# Oven_Control.net
KiCad netlist of a schematic drawn in EAGLE
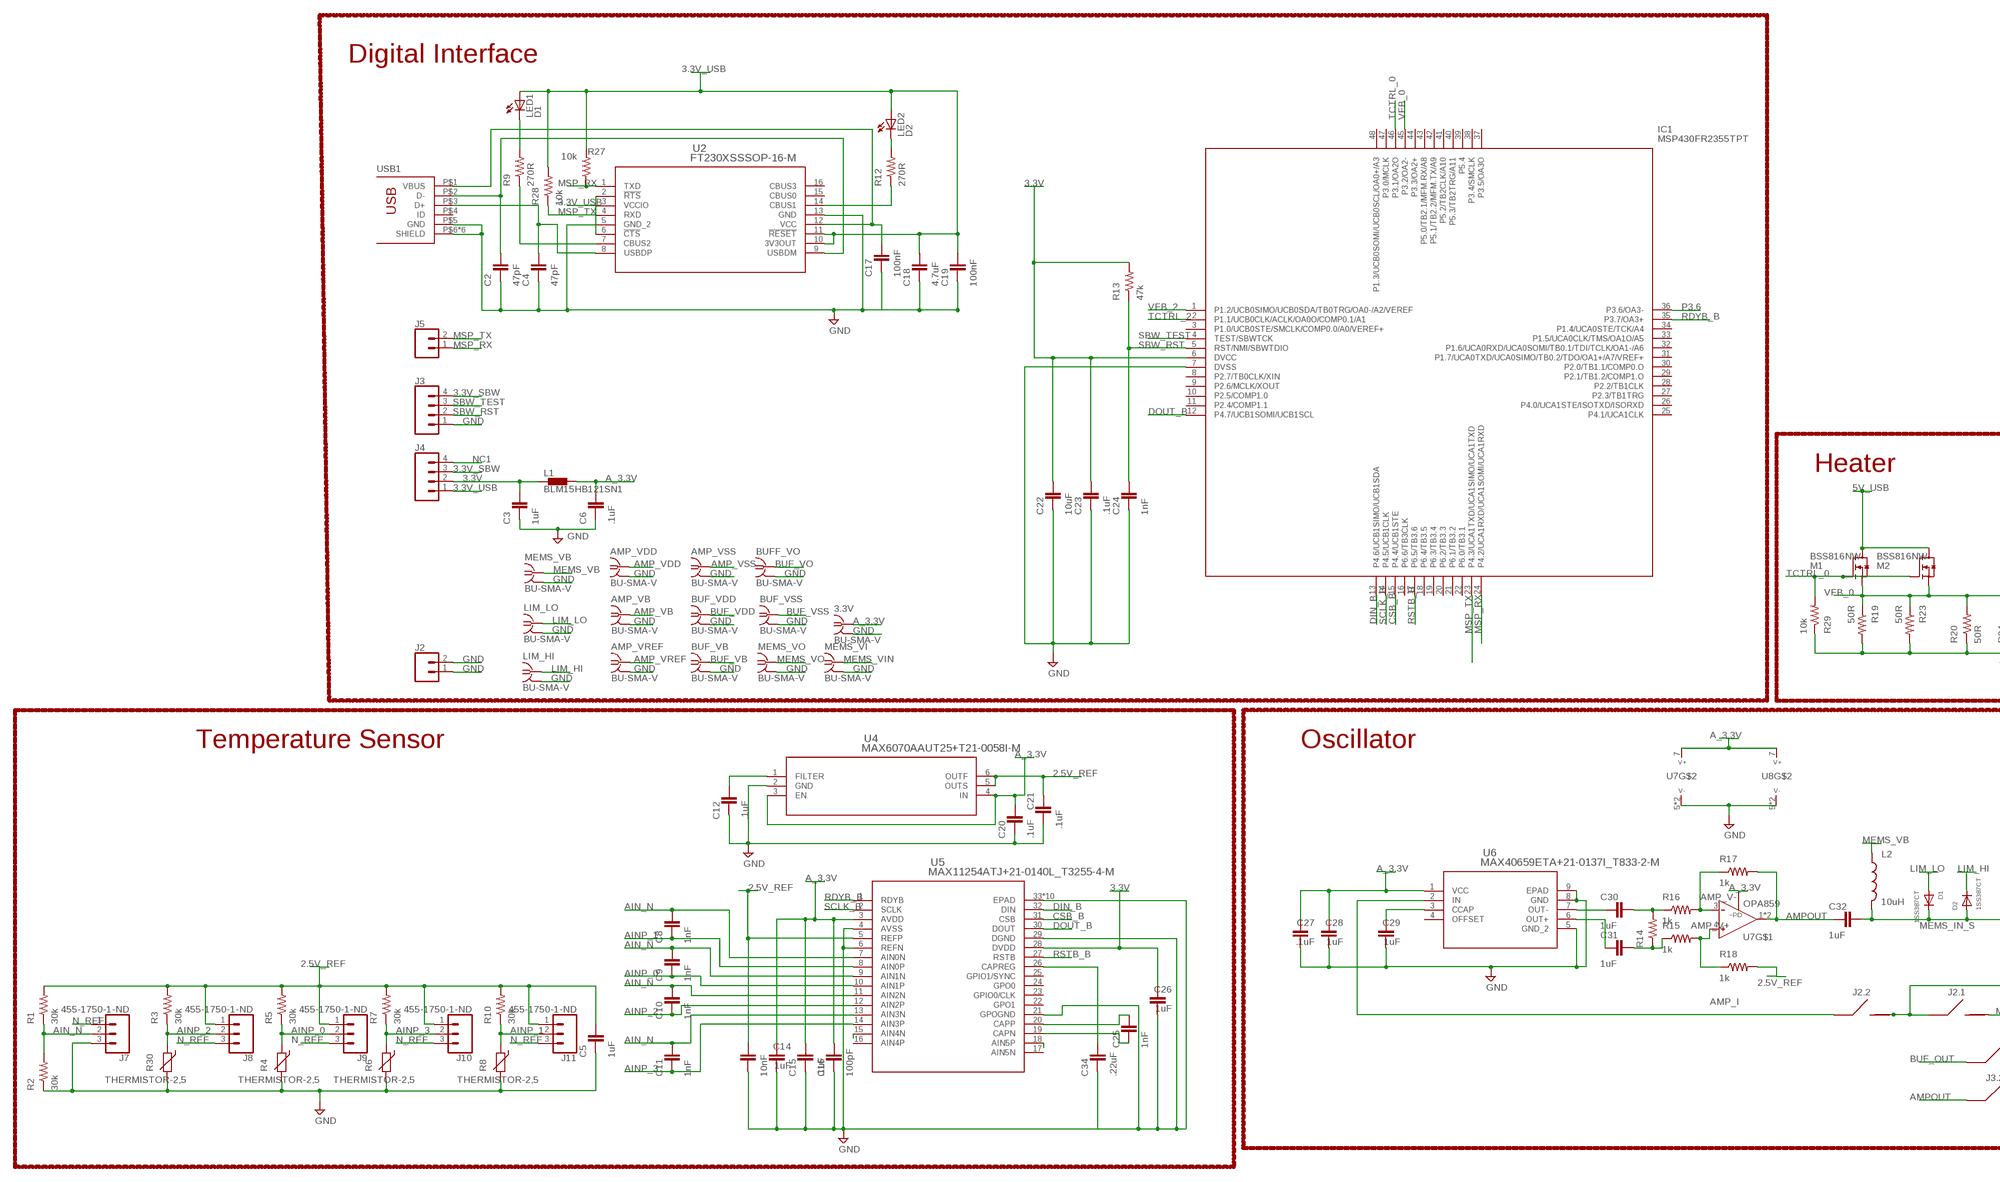
[diagram p0: schematic, sheet 1, part 1 of 2]
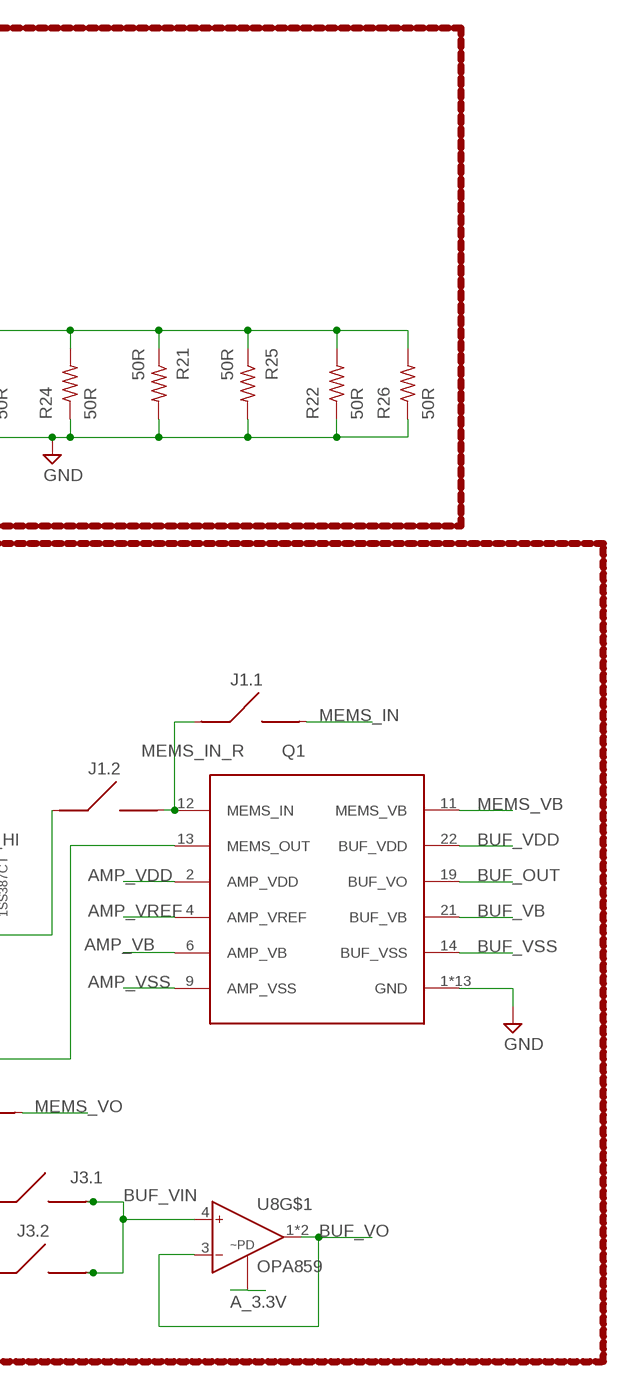
[diagram p1: schematic, sheet 1, part 2 of 2]

(export (version "E")
  (design (tool "Eeschema 10.0.6"))
  (components
    (comp (ref "3.3V")
      (value "BU-SMA-V")
      (footprint "eagle-import:BU-SMA-V")
      (libsource (lib "eagle-import") (part "BU-SMA-V"))
    )
    (comp (ref "AMP_VB")
      (value "BU-SMA-V")
      (footprint "eagle-import:BU-SMA-V")
      (libsource (lib "eagle-import") (part "BU-SMA-V"))
    )
    (comp (ref "AMP_VDD")
      (value "BU-SMA-V")
      (footprint "eagle-import:BU-SMA-V")
      (libsource (lib "eagle-import") (part "BU-SMA-V"))
    )
    (comp (ref "AMP_VREF")
      (value "BU-SMA-V")
      (footprint "eagle-import:BU-SMA-V")
      (libsource (lib "eagle-import") (part "BU-SMA-V"))
    )
    (comp (ref "AMP_VSS")
      (value "BU-SMA-V")
      (footprint "eagle-import:BU-SMA-V")
      (libsource (lib "eagle-import") (part "BU-SMA-V"))
    )
    (comp (ref "BUFF_VO")
      (value "BU-SMA-V")
      (footprint "eagle-import:BU-SMA-V")
      (libsource (lib "eagle-import") (part "BU-SMA-V"))
    )
    (comp (ref "BUF_VB")
      (value "BU-SMA-V")
      (footprint "eagle-import:BU-SMA-V")
      (libsource (lib "eagle-import") (part "BU-SMA-V"))
    )
    (comp (ref "BUF_VDD")
      (value "BU-SMA-V")
      (footprint "eagle-import:BU-SMA-V")
      (libsource (lib "eagle-import") (part "BU-SMA-V"))
    )
    (comp (ref "BUF_VSS")
      (value "BU-SMA-V")
      (footprint "eagle-import:BU-SMA-V")
      (libsource (lib "eagle-import") (part "BU-SMA-V"))
    )
    (comp (ref "C2")
      (value "47pF")
      (footprint "eagle-import:0402-CAP")
      (libsource (lib "eagle-import") (part "CAP0402-CAP"))
    )
    (comp (ref "C3")
      (value "1uF")
      (footprint "eagle-import:0402-CAP")
      (libsource (lib "eagle-import") (part "CAP0402-CAP"))
    )
    (comp (ref "C4")
      (value "47pF")
      (footprint "eagle-import:0402-CAP")
      (libsource (lib "eagle-import") (part "CAP0402-CAP"))
    )
    (comp (ref "C5")
      (value "1uF")
      (footprint "eagle-import:0402-CAP")
      (libsource (lib "eagle-import") (part "CAP0402-CAP"))
    )
    (comp (ref "C6")
      (value ".1uF")
      (footprint "eagle-import:0402-CAP")
      (libsource (lib "eagle-import") (part "CAP0402-CAP"))
    )
    (comp (ref "C8")
      (value "1nF")
      (footprint "eagle-import:0402-CAP")
      (libsource (lib "eagle-import") (part "CAP0402-CAP"))
    )
    (comp (ref "C9")
      (value "1nF")
      (footprint "eagle-import:0402-CAP")
      (libsource (lib "eagle-import") (part "CAP0402-CAP"))
    )
    (comp (ref "C10")
      (value "1nF")
      (footprint "eagle-import:0402-CAP")
      (libsource (lib "eagle-import") (part "CAP0402-CAP"))
    )
    (comp (ref "C11")
      (value "1nF")
      (footprint "eagle-import:0402-CAP")
      (libsource (lib "eagle-import") (part "CAP0402-CAP"))
    )
    (comp (ref "C12")
      (value ".1uF")
      (footprint "eagle-import:0402-CAP")
      (libsource (lib "eagle-import") (part "CAP0402-CAP"))
    )
    (comp (ref "C13")
      (value "10nF")
      (footprint "eagle-import:0402-CAP")
      (libsource (lib "eagle-import") (part "CAP0402-CAP"))
    )
    (comp (ref "C14")
      (value "1uF")
      (footprint "eagle-import:0402-CAP")
      (libsource (lib "eagle-import") (part "CAP0402-CAP"))
    )
    (comp (ref "C15")
      (value ".1uF")
      (footprint "eagle-import:0402-CAP")
      (libsource (lib "eagle-import") (part "CAP0402-CAP"))
    )
    (comp (ref "C16")
      (value "100pF")
      (footprint "eagle-import:0402-CAP")
      (libsource (lib "eagle-import") (part "CAP0402-CAP"))
    )
    (comp (ref "C17")
      (value "100nF")
      (footprint "eagle-import:0402-CAP")
      (libsource (lib "eagle-import") (part "CAP0402-CAP"))
    )
    (comp (ref "C18")
      (value "4.7uF")
      (footprint "eagle-import:0402-CAP")
      (libsource (lib "eagle-import") (part "CAP0402-CAP"))
    )
    (comp (ref "C19")
      (value "100nF")
      (footprint "eagle-import:0402-CAP")
      (libsource (lib "eagle-import") (part "CAP0402-CAP"))
    )
    (comp (ref "C20")
      (value ".1uF")
      (footprint "eagle-import:0402-CAP")
      (libsource (lib "eagle-import") (part "CAP0402-CAP"))
    )
    (comp (ref "C21")
      (value ".1uF")
      (footprint "eagle-import:0402-CAP")
      (libsource (lib "eagle-import") (part "CAP0402-CAP"))
    )
    (comp (ref "C22")
      (value "10uF")
      (footprint "eagle-import:0603-CAP")
      (libsource (lib "eagle-import") (part "CAP0603-CAP"))
    )
    (comp (ref "C23")
      (value ".1uF")
      (footprint "eagle-import:0402-CAP")
      (libsource (lib "eagle-import") (part "CAP0402-CAP"))
    )
    (comp (ref "C24")
      (value "1nF")
      (footprint "eagle-import:0402-CAP")
      (libsource (lib "eagle-import") (part "CAP0402-CAP"))
    )
    (comp (ref "C25")
      (value "1nF")
      (footprint "eagle-import:0402-CAP")
      (libsource (lib "eagle-import") (part "CAP0402-CAP"))
    )
    (comp (ref "C26")
      (value "1uF")
      (footprint "eagle-import:0402-CAP")
      (libsource (lib "eagle-import") (part "CAP0402-CAP"))
    )
    (comp (ref "C27")
      (value ".1uF")
      (footprint "eagle-import:0402-CAP")
      (libsource (lib "eagle-import") (part "CAP0402-CAP"))
    )
    (comp (ref "C28")
      (value "1uF")
      (footprint "eagle-import:0402-CAP")
      (libsource (lib "eagle-import") (part "CAP0402-CAP"))
    )
    (comp (ref "C29")
      (value "1uF")
      (footprint "eagle-import:0402-CAP")
      (libsource (lib "eagle-import") (part "CAP0402-CAP"))
    )
    (comp (ref "C30")
      (value "1uF")
      (footprint "eagle-import:0402-CAP")
      (libsource (lib "eagle-import") (part "CAP0402-CAP"))
    )
    (comp (ref "C31")
      (value "1uF")
      (footprint "eagle-import:0402-CAP")
      (libsource (lib "eagle-import") (part "CAP0402-CAP"))
    )
    (comp (ref "C32")
      (value "1uF")
      (footprint "eagle-import:0402-CAP")
      (libsource (lib "eagle-import") (part "CAP0402-CAP"))
    )
    (comp (ref "C34")
      (value ".22uF")
      (footprint "eagle-import:0402-CAP")
      (libsource (lib "eagle-import") (part "CAP0402-CAP"))
    )
    (comp (ref "D1")
      (value "1SS387CT")
      (footprint "eagle-import:SOD-882")
      (libsource (lib "eagle-import") (part "1SS387CT"))
    )
    (comp (ref "D2")
      (value "1SS387CT")
      (footprint "eagle-import:SOD-882")
      (libsource (lib "eagle-import") (part "1SS387CT"))
    )
    (comp (ref "IC1")
      (value "MSP430FR2355TPT")
      (footprint "eagle-import:QFP50P900X900X145-48N")
      (libsource (lib "eagle-import") (part "MSP430FR2355TPT"))
    )
    (comp (ref "J1.1")
      (value "0OHM_R")
      (footprint "eagle-import:R0402")
      (libsource (lib "eagle-import") (part "0OHM_R"))
    )
    (comp (ref "J1.2")
      (value "0OHM_R")
      (footprint "eagle-import:R0402")
      (libsource (lib "eagle-import") (part "0OHM_R"))
    )
    (comp (ref "J2")
      (value "CONN_02")
      (footprint "eagle-import:1X02")
      (libsource (lib "eagle-import") (part "CONN_02"))
    )
    (comp (ref "J2.1")
      (value "0OHM_R")
      (footprint "eagle-import:R0402")
      (libsource (lib "eagle-import") (part "0OHM_R"))
    )
    (comp (ref "J2.2")
      (value "0OHM_R")
      (footprint "eagle-import:R0402")
      (libsource (lib "eagle-import") (part "0OHM_R"))
    )
    (comp (ref "J3")
      (value "CONN_04")
      (footprint "eagle-import:1X04")
      (libsource (lib "eagle-import") (part "CONN_04"))
    )
    (comp (ref "J3.1")
      (value "0OHM_R")
      (footprint "eagle-import:R0402")
      (libsource (lib "eagle-import") (part "0OHM_R"))
    )
    (comp (ref "J3.2")
      (value "0OHM_R")
      (footprint "eagle-import:R0402")
      (libsource (lib "eagle-import") (part "0OHM_R"))
    )
    (comp (ref "J4")
      (value "CONN_04")
      (footprint "eagle-import:1X04")
      (libsource (lib "eagle-import") (part "CONN_04"))
    )
    (comp (ref "J5")
      (value "CONN_02")
      (footprint "eagle-import:1X02")
      (libsource (lib "eagle-import") (part "CONN_02"))
    )
    (comp (ref "J7")
      (value "455-1750-1-ND")
      (footprint "eagle-import:1X03")
      (libsource (lib "eagle-import") (part "CONN_03"))
    )
    (comp (ref "J8")
      (value "455-1750-1-ND")
      (footprint "eagle-import:1X03")
      (libsource (lib "eagle-import") (part "CONN_03"))
    )
    (comp (ref "J9")
      (value "455-1750-1-ND")
      (footprint "eagle-import:1X03")
      (libsource (lib "eagle-import") (part "CONN_03"))
    )
    (comp (ref "J10")
      (value "455-1750-1-ND")
      (footprint "eagle-import:1X03")
      (libsource (lib "eagle-import") (part "CONN_03"))
    )
    (comp (ref "J11")
      (value "455-1750-1-ND")
      (footprint "eagle-import:1X03")
      (libsource (lib "eagle-import") (part "CONN_03"))
    )
    (comp (ref "L1")
      (value "BLM15HB121SN1")
      (footprint "eagle-import:0402")
      (libsource (lib "eagle-import") (part "BLM15HB121SN1"))
    )
    (comp (ref "L2")
      (value "10uH")
      (footprint "eagle-import:R0805")
      (libsource (lib "eagle-import") (part "INDUCTOR_0805"))
    )
    (comp (ref "LED1")
      (value "D1")
      (footprint "eagle-import:CHIPLED_0603")
      (libsource (lib "eagle-import") (part "LEDCHIPLED_0603"))
    )
    (comp (ref "LED2")
      (value "D2")
      (footprint "eagle-import:CHIPLED_0603")
      (libsource (lib "eagle-import") (part "LEDCHIPLED_0603"))
    )
    (comp (ref "LIM_HI")
      (value "BU-SMA-V")
      (footprint "eagle-import:BU-SMA-V")
      (libsource (lib "eagle-import") (part "BU-SMA-V"))
    )
    (comp (ref "LIM_LO")
      (value "BU-SMA-V")
      (footprint "eagle-import:BU-SMA-V")
      (libsource (lib "eagle-import") (part "BU-SMA-V"))
    )
    (comp (ref "M1")
      (value "BSS816NW")
      (footprint "eagle-import:SOT-323")
      (libsource (lib "eagle-import") (part "BSS816NW"))
    )
    (comp (ref "M2")
      (value "BSS816NW")
      (footprint "eagle-import:SOT-323")
      (libsource (lib "eagle-import") (part "BSS816NW"))
    )
    (comp (ref "MEMS_VB")
      (value "BU-SMA-V")
      (footprint "eagle-import:BU-SMA-V")
      (libsource (lib "eagle-import") (part "BU-SMA-V"))
    )
    (comp (ref "MEMS_VI")
      (value "BU-SMA-V")
      (footprint "eagle-import:BU-SMA-V")
      (libsource (lib "eagle-import") (part "BU-SMA-V"))
    )
    (comp (ref "MEMS_VO")
      (value "BU-SMA-V")
      (footprint "eagle-import:BU-SMA-V")
      (libsource (lib "eagle-import") (part "BU-SMA-V"))
    )
    (comp (ref "Q1")
      (value "MEMS_RESONATOR")
      (footprint "eagle-import:DIL24")
      (libsource (lib "eagle-import") (part "MEMS_RESONATOR"))
    )
    (comp (ref "R1")
      (value "30k")
      (footprint "eagle-import:R0603")
      (fields (field (name "MANUFACTURER") "Rohm Semiconductor"))
      (libsource (lib "eagle-import") (part "R-US_R0603"))
    )
    (comp (ref "R2")
      (value "30k")
      (footprint "eagle-import:R0603")
      (fields (field (name "MANUFACTURER") "Rohm Semiconductor"))
      (libsource (lib "eagle-import") (part "R-US_R0603"))
    )
    (comp (ref "R3")
      (value "30k")
      (footprint "eagle-import:R0603")
      (fields (field (name "MANUFACTURER") "Rohm Semiconductor"))
      (libsource (lib "eagle-import") (part "R-US_R0603"))
    )
    (comp (ref "R4")
      (value "THERMISTOR-2,5")
      (footprint "eagle-import:RS-2,5")
      (fields (field (name "PART_NO") "NXRT15WB473FA1B030"))
      (libsource (lib "eagle-import") (part "THERMISTOR-2,5"))
    )
    (comp (ref "R5")
      (value "30k")
      (footprint "eagle-import:R0603")
      (fields (field (name "MANUFACTURER") "Rohm Semiconductor"))
      (libsource (lib "eagle-import") (part "R-US_R0603"))
    )
    (comp (ref "R6")
      (value "THERMISTOR-2,5")
      (footprint "eagle-import:RS-2,5")
      (fields (field (name "PART_NO") "NXRT15WB473FA1B030"))
      (libsource (lib "eagle-import") (part "THERMISTOR-2,5"))
    )
    (comp (ref "R7")
      (value "30k")
      (footprint "eagle-import:R0603")
      (fields (field (name "MANUFACTURER") "Rohm Semiconductor"))
      (libsource (lib "eagle-import") (part "R-US_R0603"))
    )
    (comp (ref "R8")
      (value "THERMISTOR-2,5")
      (footprint "eagle-import:RS-2,5")
      (fields (field (name "PART_NO") "NXRT15WB473FA1B030"))
      (libsource (lib "eagle-import") (part "THERMISTOR-2,5"))
    )
    (comp (ref "R9")
      (value "270R")
      (footprint "eagle-import:R0603")
      (fields (field (name "MANUFACTURER") "Rohm Semiconductor"))
      (libsource (lib "eagle-import") (part "R-US_R0603"))
    )
    (comp (ref "R10")
      (value "30k")
      (footprint "eagle-import:R0603")
      (fields (field (name "MANUFACTURER") "Rohm Semiconductor"))
      (libsource (lib "eagle-import") (part "R-US_R0603"))
    )
    (comp (ref "R12")
      (value "270R")
      (footprint "eagle-import:R0603")
      (fields (field (name "MANUFACTURER") "Rohm Semiconductor"))
      (libsource (lib "eagle-import") (part "R-US_R0603"))
    )
    (comp (ref "R13")
      (value "47k")
      (footprint "eagle-import:R0603")
      (fields (field (name "MANUFACTURER") "Rohm Semiconductor"))
      (libsource (lib "eagle-import") (part "R-US_R0603"))
    )
    (comp (ref "R14")
      (value "150R")
      (footprint "eagle-import:R0402")
      (libsource (lib "eagle-import") (part "R-US_R0402"))
    )
    (comp (ref "R15")
      (value "1k")
      (footprint "eagle-import:R0402")
      (libsource (lib "eagle-import") (part "R-US_R0402"))
    )
    (comp (ref "R16")
      (value "1k")
      (footprint "eagle-import:R0402")
      (libsource (lib "eagle-import") (part "R-US_R0402"))
    )
    (comp (ref "R17")
      (value "1k")
      (footprint "eagle-import:R0402")
      (libsource (lib "eagle-import") (part "R-US_R0402"))
    )
    (comp (ref "R18")
      (value "1k")
      (footprint "eagle-import:R0402")
      (libsource (lib "eagle-import") (part "R-US_R0402"))
    )
    (comp (ref "R19")
      (value "50R")
      (footprint "eagle-import:R1206")
      (libsource (lib "eagle-import") (part "R-US_R1206"))
    )
    (comp (ref "R20")
      (value "50R")
      (footprint "eagle-import:R1206")
      (libsource (lib "eagle-import") (part "R-US_R1206"))
    )
    (comp (ref "R21")
      (value "50R")
      (footprint "eagle-import:R1206")
      (libsource (lib "eagle-import") (part "R-US_R1206"))
    )
    (comp (ref "R22")
      (value "50R")
      (footprint "eagle-import:R1206")
      (libsource (lib "eagle-import") (part "R-US_R1206"))
    )
    (comp (ref "R23")
      (value "50R")
      (footprint "eagle-import:R1206")
      (libsource (lib "eagle-import") (part "R-US_R1206"))
    )
    (comp (ref "R24")
      (value "50R")
      (footprint "eagle-import:R1206")
      (libsource (lib "eagle-import") (part "R-US_R1206"))
    )
    (comp (ref "R25")
      (value "50R")
      (footprint "eagle-import:R1206")
      (libsource (lib "eagle-import") (part "R-US_R1206"))
    )
    (comp (ref "R26")
      (value "50R")
      (footprint "eagle-import:R1206")
      (libsource (lib "eagle-import") (part "R-US_R1206"))
    )
    (comp (ref "R27")
      (value "10k")
      (footprint "eagle-import:R0402")
      (libsource (lib "eagle-import") (part "R-US_R0402"))
    )
    (comp (ref "R28")
      (value "10k")
      (footprint "eagle-import:R0402")
      (libsource (lib "eagle-import") (part "R-US_R0402"))
    )
    (comp (ref "R29")
      (value "10k")
      (footprint "eagle-import:R0402")
      (libsource (lib "eagle-import") (part "R-US_R0402"))
    )
    (comp (ref "R30")
      (value "THERMISTOR-2,5")
      (footprint "eagle-import:RS-2,5")
      (fields (field (name "PART_NO") "NXRT15WB473FA1B030"))
      (libsource (lib "eagle-import") (part "THERMISTOR-2,5"))
    )
    (comp (ref "U2")
      (value "FT230XSSSOP-16-M")
      (footprint "eagle-import:SSOP-16-M")
      (fields (field (name "MANUFACTURER_PART_NUMBER") "FT230XS"))
      (libsource (lib "eagle-import") (part "FT230XSSSOP-16-M"))
    )
    (comp (ref "U4")
      (value "MAX6070AAUT25+T21-0058I-M")
      (footprint "eagle-import:21-0058I-M")
      (fields (field (name "MANUFACTURER_PART_NUMBER") "MAX6070AAUT25+T"))
      (libsource (lib "eagle-import") (part "MAX6070AAUT25+T21-0058I-M"))
    )
    (comp (ref "U5")
      (value "MAX11254ATJ+21-0140L_T3255-4-M")
      (footprint "eagle-import:21-0140L_T3255-4-M")
      (fields (field (name "MANUFACTURER_PART_NUMBER") "MAX11254ATJ+"))
      (libsource (lib "eagle-import") (part "MAX11254ATJ+21-0140L_T3255-4-M"))
    )
    (comp (ref "U6")
      (value "MAX40659ETA+21-0137I_T833-2-M")
      (footprint "eagle-import:21-0137I_T833-2-M")
      (fields (field (name "MANUFACTURER_PART_NUMBER") "MAX40659ETA+"))
      (libsource (lib "eagle-import") (part "MAX40659ETA+21-0137I_T833-2-M"))
    )
    (comp (ref "U7")
      (value "OPA859")
      (footprint "eagle-import:SON50P200X200X80-9N")
      (fields (field (name "SPICEPREFIX") "E"))
      (libsource (lib "eagle-import") (part "OPA859"))
    )
    (comp (ref "U8")
      (value "OPA859")
      (footprint "eagle-import:SON50P200X200X80-9N")
      (libsource (lib "eagle-import") (part "OPA859"))
    )
    (comp (ref "USB1")
      (value "USB-OTGMICRO-AB")
      (footprint "eagle-import:USB-MICRO-AB")
      (libsource (lib "eagle-import") (part "USB-OTGMICRO-AB"))
    )
  )
  (nets
    (net (code "1") (name "/2.5V_REF") (class "Default")
      (node (ref "C13") (pin "2") (pinfunction "2_2") (pintype "passive"))
      (node (ref "C21") (pin "2") (pinfunction "2_2") (pintype "passive"))
      (node (ref "C5") (pin "2") (pinfunction "2_2") (pintype "passive"))
      (node (ref "J10") (pin "1") (pinfunction "1_1") (pintype "passive"))
      (node (ref "J11") (pin "1") (pinfunction "1_1") (pintype "passive"))
      (node (ref "J8") (pin "1") (pinfunction "1_1") (pintype "passive"))
      (node (ref "J9") (pin "1") (pinfunction "1_1") (pintype "passive"))
      (node (ref "R1") (pin "2") (pinfunction "2_2") (pintype "passive"))
      (node (ref "R10") (pin "2") (pinfunction "2_2") (pintype "passive"))
      (node (ref "R18") (pin "2") (pinfunction "2_2") (pintype "passive"))
      (node (ref "R3") (pin "2") (pinfunction "2_2") (pintype "passive"))
      (node (ref "R5") (pin "2") (pinfunction "2_2") (pintype "passive"))
      (node (ref "R7") (pin "2") (pinfunction "2_2") (pintype "passive"))
      (node (ref "U4") (pin "5") (pinfunction "OUTS_5") (pintype "output"))
      (node (ref "U4") (pin "6") (pinfunction "OUTF_6") (pintype "output"))
      (node (ref "U5") (pin "5") (pinfunction "REFP_5") (pintype "passive"))
    )
    (net (code "2") (name "/3.3V") (class "Default")
      (node (ref "C22") (pin "2") (pinfunction "2_2") (pintype "passive"))
      (node (ref "C23") (pin "2") (pinfunction "2_2") (pintype "passive"))
      (node (ref "C26") (pin "2") (pinfunction "2_2") (pintype "passive"))
      (node (ref "C3") (pin "2") (pinfunction "2_2") (pintype "passive"))
      (node (ref "IC1") (pin "6") (pinfunction "DVCC_6") (pintype "bidirectional"))
      (node (ref "J4") (pin "2") (pinfunction "2_2") (pintype "passive"))
      (node (ref "L1") (pin "1") (pinfunction "1_1") (pintype "passive"))
      (node (ref "R13") (pin "2") (pinfunction "2_2") (pintype "passive"))
      (node (ref "U5") (pin "28") (pinfunction "DVDD_28") (pintype "power_in"))
    )
    (net (code "3") (name "/3.3V_SBW") (class "Default")
      (node (ref "J3") (pin "4") (pinfunction "4_4") (pintype "passive"))
      (node (ref "J4") (pin "3") (pinfunction "3_3") (pintype "passive"))
    )
    (net (code "4") (name "/3.3V_USB") (class "Default")
      (node (ref "C18") (pin "2") (pinfunction "2_2") (pintype "passive"))
      (node (ref "C19") (pin "2") (pinfunction "2_2") (pintype "passive"))
      (node (ref "J4") (pin "1") (pinfunction "1_1") (pintype "passive"))
      (node (ref "LED1") (pin "A") (pinfunction "A_A") (pintype "passive"))
      (node (ref "LED2") (pin "A") (pinfunction "A_A") (pintype "passive"))
      (node (ref "R27") (pin "2") (pinfunction "2_2") (pintype "passive"))
      (node (ref "R28") (pin "2") (pinfunction "2_2") (pintype "passive"))
      (node (ref "U2") (pin "10") (pinfunction "3V3OUT_10") (pintype "power_in"))
      (node (ref "U2") (pin "11") (pinfunction "~{RESET}_11") (pintype "input"))
      (node (ref "U2") (pin "3") (pinfunction "VCCIO_3") (pintype "power_in"))
    )
    (net (code "5") (name "/5V_USB") (class "Default")
      (node (ref "C17") (pin "2") (pinfunction "2_2") (pintype "passive"))
      (node (ref "M1") (pin "D") (pinfunction "D_D") (pintype "passive"))
      (node (ref "M2") (pin "D") (pinfunction "D_D") (pintype "passive"))
      (node (ref "U2") (pin "12") (pinfunction "VCC_12") (pintype "power_in"))
      (node (ref "USB1") (pin "P$1") (pinfunction "VBUS_P$1") (pintype "bidirectional"))
    )
    (net (code "6") (name "/AINP_0") (class "Default")
      (node (ref "C9") (pin "1") (pinfunction "1_1") (pintype "passive"))
      (node (ref "J9") (pin "2") (pinfunction "2_2") (pintype "passive"))
      (node (ref "R4") (pin "1") (pinfunction "1_1") (pintype "passive"))
      (node (ref "R5") (pin "1") (pinfunction "1_1") (pintype "passive"))
      (node (ref "U5") (pin "10") (pinfunction "AIN1P_10") (pintype "input"))
    )
    (net (code "7") (name "/AINP_1") (class "Default")
      (node (ref "C8") (pin "1") (pinfunction "1_1") (pintype "passive"))
      (node (ref "J11") (pin "2") (pinfunction "2_2") (pintype "passive"))
      (node (ref "R10") (pin "1") (pinfunction "1_1") (pintype "passive"))
      (node (ref "R8") (pin "1") (pinfunction "1_1") (pintype "passive"))
      (node (ref "U5") (pin "8") (pinfunction "AIN0P_8") (pintype "bidirectional"))
    )
    (net (code "8") (name "/AINP_2") (class "Default")
      (node (ref "C10") (pin "1") (pinfunction "1_1") (pintype "passive"))
      (node (ref "J8") (pin "2") (pinfunction "2_2") (pintype "passive"))
      (node (ref "R3") (pin "1") (pinfunction "1_1") (pintype "passive"))
      (node (ref "R30") (pin "1") (pinfunction "1_1") (pintype "passive"))
      (node (ref "U5") (pin "12") (pinfunction "AIN2P_12") (pintype "input"))
    )
    (net (code "9") (name "/AINP_3") (class "Default")
      (node (ref "C11") (pin "1") (pinfunction "1_1") (pintype "passive"))
      (node (ref "J10") (pin "2") (pinfunction "2_2") (pintype "passive"))
      (node (ref "R6") (pin "1") (pinfunction "1_1") (pintype "passive"))
      (node (ref "R7") (pin "1") (pinfunction "1_1") (pintype "passive"))
      (node (ref "U5") (pin "14") (pinfunction "AIN3P_14") (pintype "input"))
    )
    (net (code "10") (name "/AIN_N") (class "Default")
      (node (ref "C10") (pin "2") (pinfunction "2_2") (pintype "passive"))
      (node (ref "C11") (pin "2") (pinfunction "2_2") (pintype "passive"))
      (node (ref "C8") (pin "2") (pinfunction "2_2") (pintype "passive"))
      (node (ref "C9") (pin "2") (pinfunction "2_2") (pintype "passive"))
      (node (ref "J7") (pin "2") (pinfunction "2_2") (pintype "passive"))
      (node (ref "R1") (pin "1") (pinfunction "1_1") (pintype "passive"))
      (node (ref "R2") (pin "2") (pinfunction "2_2") (pintype "passive"))
      (node (ref "U5") (pin "11") (pinfunction "AIN2N_11") (pintype "input"))
      (node (ref "U5") (pin "13") (pinfunction "AIN3N_13") (pintype "input"))
      (node (ref "U5") (pin "7") (pinfunction "AIN0N_7") (pintype "bidirectional"))
      (node (ref "U5") (pin "9") (pinfunction "AIN1N_9") (pintype "input"))
    )
    (net (code "11") (name "/AMPOUT") (class "Default")
      (node (ref "C32") (pin "1") (pinfunction "1_1") (pintype "passive"))
      (node (ref "J3.2") (pin "1") (pinfunction "P$1_1") (pintype "bidirectional"))
      (node (ref "R17") (pin "2") (pinfunction "2_2") (pintype "passive"))
      (node (ref "U7") (pin "1") (pinfunction "OUT_1") (pintype "output"))
      (node (ref "U7") (pin "6") (pinfunction "OUT_6") (pintype "output"))
    )
    (net (code "12") (name "/AMP_I") (class "Default")
      (node (ref "J2.2") (pin "1") (pinfunction "P$1_1") (pintype "bidirectional"))
      (node (ref "U6") (pin "2") (pinfunction "IN_2") (pintype "passive"))
    )
    (net (code "13") (name "/AMP_V+") (class "Default")
      (node (ref "R15") (pin "2") (pinfunction "2_2") (pintype "passive"))
      (node (ref "R18") (pin "1") (pinfunction "1_1") (pintype "passive"))
      (node (ref "U7") (pin "4") (pinfunction "IN+_4") (pintype "input"))
    )
    (net (code "14") (name "/AMP_V-") (class "Default")
      (node (ref "R16") (pin "2") (pinfunction "2_2") (pintype "passive"))
      (node (ref "R17") (pin "1") (pinfunction "1_1") (pintype "passive"))
      (node (ref "U7") (pin "3") (pinfunction "IN-_3") (pintype "input"))
    )
    (net (code "15") (name "/AMP_VB") (class "Default")
      (node (ref "AMP_VB") (pin "1") (pinfunction "1_1") (pintype "passive"))
      (node (ref "Q1") (pin "6") (pinfunction "AMP_VB_6") (pintype "bidirectional"))
    )
    (net (code "16") (name "/AMP_VDD") (class "Default")
      (node (ref "AMP_VDD") (pin "1") (pinfunction "1_1") (pintype "passive"))
      (node (ref "Q1") (pin "2") (pinfunction "AMP_VDD_2") (pintype "bidirectional"))
    )
    (net (code "17") (name "/AMP_VREF") (class "Default")
      (node (ref "AMP_VREF") (pin "1") (pinfunction "1_1") (pintype "passive"))
      (node (ref "Q1") (pin "4") (pinfunction "AMP_VREF_4") (pintype "bidirectional"))
    )
    (net (code "18") (name "/AMP_VSS") (class "Default")
      (node (ref "AMP_VSS") (pin "1") (pinfunction "1_1") (pintype "passive"))
      (node (ref "Q1") (pin "9") (pinfunction "AMP_VSS_9") (pintype "bidirectional"))
    )
    (net (code "19") (name "/A_3.3V") (class "Default")
      (node (ref "3.3V") (pin "1") (pinfunction "1_1") (pintype "passive"))
      (node (ref "C14") (pin "2") (pinfunction "2_2") (pintype "passive"))
      (node (ref "C15") (pin "2") (pinfunction "2_2") (pintype "passive"))
      (node (ref "C16") (pin "2") (pinfunction "2_2") (pintype "passive"))
      (node (ref "C20") (pin "2") (pinfunction "2_2") (pintype "passive"))
      (node (ref "C27") (pin "2") (pinfunction "2_2") (pintype "passive"))
      (node (ref "C28") (pin "2") (pinfunction "2_2") (pintype "passive"))
      (node (ref "C6") (pin "2") (pinfunction "2_2") (pintype "passive"))
      (node (ref "L1") (pin "2") (pinfunction "2_2") (pintype "passive"))
      (node (ref "U4") (pin "3") (pinfunction "EN_3") (pintype "passive"))
      (node (ref "U4") (pin "4") (pinfunction "IN_4") (pintype "input"))
      (node (ref "U5") (pin "3") (pinfunction "AVDD_3") (pintype "power_in"))
      (node (ref "U6") (pin "1") (pinfunction "VCC_1") (pintype "power_in"))
      (node (ref "U7") (pin "7") (pinfunction "V+_7") (pintype "power_in"))
      (node (ref "U7") (pin "8") (pinfunction "P$1_8") (pintype "bidirectional"))
      (node (ref "U8") (pin "7") (pinfunction "V+_7") (pintype "power_in"))
      (node (ref "U8") (pin "8") (pinfunction "P$1_8") (pintype "bidirectional"))
    )
    (net (code "20") (name "/BUF_OUT") (class "Default")
      (node (ref "J3.1") (pin "1") (pinfunction "P$1_1") (pintype "bidirectional"))
      (node (ref "Q1") (pin "19") (pinfunction "BUF_VO_19") (pintype "bidirectional"))
    )
    (net (code "21") (name "/BUF_VB") (class "Default")
      (node (ref "BUF_VB") (pin "1") (pinfunction "1_1") (pintype "passive"))
      (node (ref "Q1") (pin "21") (pinfunction "BUF_VB_21") (pintype "bidirectional"))
    )
    (net (code "22") (name "/BUF_VDD") (class "Default")
      (node (ref "BUF_VDD") (pin "1") (pinfunction "1_1") (pintype "passive"))
      (node (ref "Q1") (pin "22") (pinfunction "BUF_VDD_22") (pintype "bidirectional"))
    )
    (net (code "23") (name "/BUF_VIN") (class "Default")
      (node (ref "J3.1") (pin "2") (pinfunction "P$2_2") (pintype "bidirectional"))
      (node (ref "J3.2") (pin "2") (pinfunction "P$2_2") (pintype "bidirectional"))
      (node (ref "U8") (pin "4") (pinfunction "IN+_4") (pintype "input"))
    )
    (net (code "24") (name "/BUF_VO") (class "Default")
      (node (ref "BUFF_VO") (pin "1") (pinfunction "1_1") (pintype "passive"))
      (node (ref "U8") (pin "1") (pinfunction "OUT_1") (pintype "output"))
      (node (ref "U8") (pin "3") (pinfunction "IN-_3") (pintype "input"))
      (node (ref "U8") (pin "6") (pinfunction "OUT_6") (pintype "output"))
    )
    (net (code "25") (name "/BUF_VSS") (class "Default")
      (node (ref "BUF_VSS") (pin "1") (pinfunction "1_1") (pintype "passive"))
      (node (ref "Q1") (pin "14") (pinfunction "BUF_VSS_14") (pintype "bidirectional"))
    )
    (net (code "26") (name "/CSB_B") (class "Default")
      (node (ref "IC1") (pin "15") (pinfunction "P4.4/UCB1STE_15") (pintype "bidirectional"))
      (node (ref "U5") (pin "31") (pinfunction "CSB_31") (pintype "passive"))
    )
    (net (code "27") (name "/DIN_B") (class "Default")
      (node (ref "IC1") (pin "13") (pinfunction "P4.6/UCB1SIMO/UCB1SDA_13") (pintype "bidirectional"))
      (node (ref "U5") (pin "32") (pinfunction "DIN_32") (pintype "passive"))
    )
    (net (code "28") (name "/DOUT_B") (class "Default")
      (node (ref "IC1") (pin "12") (pinfunction "P4.7/UCB1SOMI/UCB1SCL_12") (pintype "bidirectional"))
      (node (ref "U5") (pin "30") (pinfunction "DOUT_30") (pintype "output"))
    )
    (net (code "29") (name "/LIM_HI") (class "Default")
      (node (ref "D2") (pin "C") (pinfunction "C_C") (pintype "passive"))
      (node (ref "LIM_HI") (pin "1") (pinfunction "1_1") (pintype "passive"))
    )
    (net (code "30") (name "/LIM_LO") (class "Default")
      (node (ref "D1") (pin "A") (pinfunction "A_A") (pintype "passive"))
      (node (ref "LIM_LO") (pin "1") (pinfunction "1_1") (pintype "passive"))
    )
    (net (code "31") (name "/MEMS_IN") (class "Default")
      (node (ref "J1.1") (pin "2") (pinfunction "P$2_2") (pintype "bidirectional"))
    )
    (net (code "32") (name "/MEMS_IN_R") (class "Default")
      (node (ref "J1.1") (pin "1") (pinfunction "P$1_1") (pintype "bidirectional"))
      (node (ref "J1.2") (pin "2") (pinfunction "P$2_2") (pintype "bidirectional"))
      (node (ref "Q1") (pin "12") (pinfunction "MEMS_IN_12") (pintype "bidirectional"))
    )
    (net (code "33") (name "/MEMS_IN_S") (class "Default")
      (node (ref "C32") (pin "2") (pinfunction "2_2") (pintype "passive"))
      (node (ref "D1") (pin "C") (pinfunction "C_C") (pintype "passive"))
      (node (ref "D2") (pin "A") (pinfunction "A_A") (pintype "passive"))
      (node (ref "J1.2") (pin "1") (pinfunction "P$1_1") (pintype "bidirectional"))
      (node (ref "L2") (pin "2") (pinfunction "2_2") (pintype "passive"))
    )
    (net (code "34") (name "/MEMS_VB") (class "Default")
      (node (ref "L2") (pin "1") (pinfunction "1_1") (pintype "passive"))
      (node (ref "MEMS_VB") (pin "1") (pinfunction "1_1") (pintype "passive"))
      (node (ref "Q1") (pin "11") (pinfunction "MEMS_VB_11") (pintype "bidirectional"))
    )
    (net (code "35") (name "/MEMS_VIN") (class "Default")
      (node (ref "MEMS_VI") (pin "1") (pinfunction "1_1") (pintype "passive"))
    )
    (net (code "36") (name "/MEMS_VO") (class "Default")
      (node (ref "J2.1") (pin "2") (pinfunction "P$2_2") (pintype "bidirectional"))
      (node (ref "MEMS_VO") (pin "1") (pinfunction "1_1") (pintype "passive"))
    )
    (net (code "37") (name "/MSP_RX") (class "Default")
      (node (ref "IC1") (pin "24") (pinfunction "P4.2/UCA1RXD/UCA1SOMI/UCA1RXD_24") (pintype "bidirectional"))
      (node (ref "J5") (pin "1") (pinfunction "1_1") (pintype "passive"))
      (node (ref "R27") (pin "1") (pinfunction "1_1") (pintype "passive"))
      (node (ref "U2") (pin "1") (pinfunction "TXD_1") (pintype "output"))
    )
    (net (code "38") (name "/MSP_TX") (class "Default")
      (node (ref "IC1") (pin "23") (pinfunction "P4.3/UCA1TXD/UCA1SIMO/UCA1TXD_23") (pintype "bidirectional"))
      (node (ref "J5") (pin "2") (pinfunction "2_2") (pintype "passive"))
      (node (ref "R28") (pin "1") (pinfunction "1_1") (pintype "passive"))
      (node (ref "U2") (pin "4") (pinfunction "RXD_4") (pintype "input"))
    )
    (net (code "39") (name "/NC1") (class "Default")
      (node (ref "J4") (pin "4") (pinfunction "4_4") (pintype "passive"))
    )
    (net (code "40") (name "/N_REF") (class "Default")
      (node (ref "J10") (pin "3") (pinfunction "3_3") (pintype "passive"))
      (node (ref "J11") (pin "3") (pinfunction "3_3") (pintype "passive"))
      (node (ref "J7") (pin "1") (pinfunction "1_1") (pintype "passive"))
      (node (ref "J8") (pin "3") (pinfunction "3_3") (pintype "passive"))
      (node (ref "J9") (pin "3") (pinfunction "3_3") (pintype "passive"))
    )
    (net (code "41") (name "/P3.6") (class "Default")
      (node (ref "IC1") (pin "36") (pinfunction "P3.6/OA3-_36") (pintype "bidirectional"))
    )
    (net (code "42") (name "/RDYB_B") (class "Default")
      (node (ref "IC1") (pin "35") (pinfunction "P3.7/OA3+_35") (pintype "bidirectional"))
      (node (ref "U5") (pin "1") (pinfunction "RDYB_1") (pintype "passive"))
    )
    (net (code "43") (name "/RSTB_B") (class "Default")
      (node (ref "IC1") (pin "17") (pinfunction "P6.5/TB3.6_17") (pintype "bidirectional"))
      (node (ref "U5") (pin "27") (pinfunction "RSTB_27") (pintype "passive"))
    )
    (net (code "44") (name "/SBW_RST") (class "Default")
      (node (ref "C24") (pin "2") (pinfunction "2_2") (pintype "passive"))
      (node (ref "IC1") (pin "5") (pinfunction "RST/NMI/SBWTDIO_5") (pintype "bidirectional"))
      (node (ref "J3") (pin "2") (pinfunction "2_2") (pintype "passive"))
      (node (ref "R13") (pin "1") (pinfunction "1_1") (pintype "passive"))
    )
    (net (code "45") (name "/SBW_TEST") (class "Default")
      (node (ref "IC1") (pin "4") (pinfunction "TEST/SBWTCK_4") (pintype "bidirectional"))
      (node (ref "J3") (pin "3") (pinfunction "3_3") (pintype "passive"))
    )
    (net (code "46") (name "/SCLK_B") (class "Default")
      (node (ref "IC1") (pin "14") (pinfunction "P4.5/UCB1CLK_14") (pintype "bidirectional"))
      (node (ref "U5") (pin "2") (pinfunction "SCLK_2") (pintype "passive"))
    )
    (net (code "47") (name "/TCTRL_0") (class "Default")
      (node (ref "IC1") (pin "46") (pinfunction "P3.1/OA2O_46") (pintype "bidirectional"))
      (node (ref "M1") (pin "G") (pinfunction "G_G") (pintype "passive"))
      (node (ref "M2") (pin "G") (pinfunction "G_G") (pintype "passive"))
      (node (ref "R29") (pin "2") (pinfunction "2_2") (pintype "passive"))
    )
    (net (code "48") (name "/TCTRL_2") (class "Default")
      (node (ref "IC1") (pin "2") (pinfunction "P1.1/UCB0CLK/ACLK/OA0O/COMP0.1/A1_2") (pintype "bidirectional"))
    )
    (net (code "49") (name "/VFB_0") (class "Default")
      (node (ref "IC1") (pin "45") (pinfunction "P3.2/OA2-_45") (pintype "bidirectional"))
      (node (ref "M1") (pin "S") (pinfunction "S_S") (pintype "passive"))
      (node (ref "M2") (pin "S") (pinfunction "S_S") (pintype "passive"))
      (node (ref "R19") (pin "1") (pinfunction "1_1") (pintype "passive"))
      (node (ref "R20") (pin "2") (pinfunction "2_2") (pintype "passive"))
      (node (ref "R21") (pin "1") (pinfunction "1_1") (pintype "passive"))
      (node (ref "R22") (pin "2") (pinfunction "2_2") (pintype "passive"))
      (node (ref "R23") (pin "1") (pinfunction "1_1") (pintype "passive"))
      (node (ref "R24") (pin "2") (pinfunction "2_2") (pintype "passive"))
      (node (ref "R25") (pin "1") (pinfunction "1_1") (pintype "passive"))
      (node (ref "R26") (pin "2") (pinfunction "2_2") (pintype "passive"))
    )
    (net (code "50") (name "/VFB_2") (class "Default")
      (node (ref "IC1") (pin "1") (pinfunction "P1.2/UCB0SIMO/UCB0SDA/TB0TRG/OA0-/A2/VEREF_1") (pintype "bidirectional"))
    )
    (net (code "51") (name "GND") (class "Default")
      (node (ref "3.3V") (pin "2") (pinfunction "2_2") (pintype "passive"))
      (node (ref "3.3V") (pin "3") (pinfunction "2_3") (pintype "passive"))
      (node (ref "3.3V") (pin "4") (pinfunction "2_4") (pintype "passive"))
      (node (ref "3.3V") (pin "5") (pinfunction "2_5") (pintype "passive"))
      (node (ref "AMP_VB") (pin "2") (pinfunction "2_2") (pintype "passive"))
      (node (ref "AMP_VB") (pin "3") (pinfunction "2_3") (pintype "passive"))
      (node (ref "AMP_VB") (pin "4") (pinfunction "2_4") (pintype "passive"))
      (node (ref "AMP_VB") (pin "5") (pinfunction "2_5") (pintype "passive"))
      (node (ref "AMP_VDD") (pin "2") (pinfunction "2_2") (pintype "passive"))
      (node (ref "AMP_VDD") (pin "3") (pinfunction "2_3") (pintype "passive"))
      (node (ref "AMP_VDD") (pin "4") (pinfunction "2_4") (pintype "passive"))
      (node (ref "AMP_VDD") (pin "5") (pinfunction "2_5") (pintype "passive"))
      (node (ref "AMP_VREF") (pin "2") (pinfunction "2_2") (pintype "passive"))
      (node (ref "AMP_VREF") (pin "3") (pinfunction "2_3") (pintype "passive"))
      (node (ref "AMP_VREF") (pin "4") (pinfunction "2_4") (pintype "passive"))
      (node (ref "AMP_VREF") (pin "5") (pinfunction "2_5") (pintype "passive"))
      (node (ref "AMP_VSS") (pin "2") (pinfunction "2_2") (pintype "passive"))
      (node (ref "AMP_VSS") (pin "3") (pinfunction "2_3") (pintype "passive"))
      (node (ref "AMP_VSS") (pin "4") (pinfunction "2_4") (pintype "passive"))
      (node (ref "AMP_VSS") (pin "5") (pinfunction "2_5") (pintype "passive"))
      (node (ref "BUFF_VO") (pin "2") (pinfunction "2_2") (pintype "passive"))
      (node (ref "BUFF_VO") (pin "3") (pinfunction "2_3") (pintype "passive"))
      (node (ref "BUFF_VO") (pin "4") (pinfunction "2_4") (pintype "passive"))
      (node (ref "BUFF_VO") (pin "5") (pinfunction "2_5") (pintype "passive"))
      (node (ref "BUF_VB") (pin "2") (pinfunction "2_2") (pintype "passive"))
      (node (ref "BUF_VB") (pin "3") (pinfunction "2_3") (pintype "passive"))
      (node (ref "BUF_VB") (pin "4") (pinfunction "2_4") (pintype "passive"))
      (node (ref "BUF_VB") (pin "5") (pinfunction "2_5") (pintype "passive"))
      (node (ref "BUF_VDD") (pin "2") (pinfunction "2_2") (pintype "passive"))
      (node (ref "BUF_VDD") (pin "3") (pinfunction "2_3") (pintype "passive"))
      (node (ref "BUF_VDD") (pin "4") (pinfunction "2_4") (pintype "passive"))
      (node (ref "BUF_VDD") (pin "5") (pinfunction "2_5") (pintype "passive"))
      (node (ref "BUF_VSS") (pin "2") (pinfunction "2_2") (pintype "passive"))
      (node (ref "BUF_VSS") (pin "3") (pinfunction "2_3") (pintype "passive"))
      (node (ref "BUF_VSS") (pin "4") (pinfunction "2_4") (pintype "passive"))
      (node (ref "BUF_VSS") (pin "5") (pinfunction "2_5") (pintype "passive"))
      (node (ref "C12") (pin "1") (pinfunction "1_1") (pintype "passive"))
      (node (ref "C13") (pin "1") (pinfunction "1_1") (pintype "passive"))
      (node (ref "C14") (pin "1") (pinfunction "1_1") (pintype "passive"))
      (node (ref "C15") (pin "1") (pinfunction "1_1") (pintype "passive"))
      (node (ref "C16") (pin "1") (pinfunction "1_1") (pintype "passive"))
      (node (ref "C17") (pin "1") (pinfunction "1_1") (pintype "passive"))
      (node (ref "C18") (pin "1") (pinfunction "1_1") (pintype "passive"))
      (node (ref "C19") (pin "1") (pinfunction "1_1") (pintype "passive"))
      (node (ref "C2") (pin "1") (pinfunction "1_1") (pintype "passive"))
      (node (ref "C20") (pin "1") (pinfunction "1_1") (pintype "passive"))
      (node (ref "C21") (pin "1") (pinfunction "1_1") (pintype "passive"))
      (node (ref "C22") (pin "1") (pinfunction "1_1") (pintype "passive"))
      (node (ref "C23") (pin "1") (pinfunction "1_1") (pintype "passive"))
      (node (ref "C24") (pin "1") (pinfunction "1_1") (pintype "passive"))
      (node (ref "C26") (pin "1") (pinfunction "1_1") (pintype "passive"))
      (node (ref "C27") (pin "1") (pinfunction "1_1") (pintype "passive"))
      (node (ref "C28") (pin "1") (pinfunction "1_1") (pintype "passive"))
      (node (ref "C29") (pin "1") (pinfunction "1_1") (pintype "passive"))
      (node (ref "C3") (pin "1") (pinfunction "1_1") (pintype "passive"))
      (node (ref "C34") (pin "1") (pinfunction "1_1") (pintype "passive"))
      (node (ref "C4") (pin "1") (pinfunction "1_1") (pintype "passive"))
      (node (ref "C5") (pin "1") (pinfunction "1_1") (pintype "passive"))
      (node (ref "C6") (pin "1") (pinfunction "1_1") (pintype "passive"))
      (node (ref "IC1") (pin "7") (pinfunction "DVSS_7") (pintype "bidirectional"))
      (node (ref "J2") (pin "1") (pinfunction "1_1") (pintype "passive"))
      (node (ref "J2") (pin "2") (pinfunction "2_2") (pintype "passive"))
      (node (ref "J3") (pin "1") (pinfunction "1_1") (pintype "passive"))
      (node (ref "J7") (pin "3") (pinfunction "3_3") (pintype "passive"))
      (node (ref "LIM_HI") (pin "2") (pinfunction "2_2") (pintype "passive"))
      (node (ref "LIM_HI") (pin "3") (pinfunction "2_3") (pintype "passive"))
      (node (ref "LIM_HI") (pin "4") (pinfunction "2_4") (pintype "passive"))
      (node (ref "LIM_HI") (pin "5") (pinfunction "2_5") (pintype "passive"))
      (node (ref "LIM_LO") (pin "2") (pinfunction "2_2") (pintype "passive"))
      (node (ref "LIM_LO") (pin "3") (pinfunction "2_3") (pintype "passive"))
      (node (ref "LIM_LO") (pin "4") (pinfunction "2_4") (pintype "passive"))
      (node (ref "LIM_LO") (pin "5") (pinfunction "2_5") (pintype "passive"))
      (node (ref "MEMS_VB") (pin "2") (pinfunction "2_2") (pintype "passive"))
      (node (ref "MEMS_VB") (pin "3") (pinfunction "2_3") (pintype "passive"))
      (node (ref "MEMS_VB") (pin "4") (pinfunction "2_4") (pintype "passive"))
      (node (ref "MEMS_VB") (pin "5") (pinfunction "2_5") (pintype "passive"))
      (node (ref "MEMS_VI") (pin "2") (pinfunction "2_2") (pintype "passive"))
      (node (ref "MEMS_VI") (pin "3") (pinfunction "2_3") (pintype "passive"))
      (node (ref "MEMS_VI") (pin "4") (pinfunction "2_4") (pintype "passive"))
      (node (ref "MEMS_VI") (pin "5") (pinfunction "2_5") (pintype "passive"))
      (node (ref "MEMS_VO") (pin "2") (pinfunction "2_2") (pintype "passive"))
      (node (ref "MEMS_VO") (pin "3") (pinfunction "2_3") (pintype "passive"))
      (node (ref "MEMS_VO") (pin "4") (pinfunction "2_4") (pintype "passive"))
      (node (ref "MEMS_VO") (pin "5") (pinfunction "2_5") (pintype "passive"))
      (node (ref "Q1") (pin "1") (pinfunction "GND_1") (pintype "bidirectional"))
      (node (ref "Q1") (pin "10") (pinfunction "GND_10") (pintype "bidirectional"))
      (node (ref "Q1") (pin "15") (pinfunction "GND_15") (pintype "bidirectional"))
      (node (ref "Q1") (pin "16") (pinfunction "GND_16") (pintype "bidirectional"))
      (node (ref "Q1") (pin "17") (pinfunction "GND_17") (pintype "bidirectional"))
      (node (ref "Q1") (pin "18") (pinfunction "GND_18") (pintype "bidirectional"))
      (node (ref "Q1") (pin "20") (pinfunction "GND_20") (pintype "bidirectional"))
      (node (ref "Q1") (pin "23") (pinfunction "GND_23") (pintype "bidirectional"))
      (node (ref "Q1") (pin "24") (pinfunction "GND_24") (pintype "bidirectional"))
      (node (ref "Q1") (pin "3") (pinfunction "GND_3") (pintype "bidirectional"))
      (node (ref "Q1") (pin "5") (pinfunction "GND_5") (pintype "bidirectional"))
      (node (ref "Q1") (pin "7") (pinfunction "GND_7") (pintype "bidirectional"))
      (node (ref "Q1") (pin "8") (pinfunction "GND_8") (pintype "bidirectional"))
      (node (ref "R19") (pin "2") (pinfunction "2_2") (pintype "passive"))
      (node (ref "R2") (pin "1") (pinfunction "1_1") (pintype "passive"))
      (node (ref "R20") (pin "1") (pinfunction "1_1") (pintype "passive"))
      (node (ref "R21") (pin "2") (pinfunction "2_2") (pintype "passive"))
      (node (ref "R22") (pin "1") (pinfunction "1_1") (pintype "passive"))
      (node (ref "R23") (pin "2") (pinfunction "2_2") (pintype "passive"))
      (node (ref "R24") (pin "1") (pinfunction "1_1") (pintype "passive"))
      (node (ref "R25") (pin "2") (pinfunction "2_2") (pintype "passive"))
      (node (ref "R26") (pin "1") (pinfunction "1_1") (pintype "passive"))
      (node (ref "R29") (pin "1") (pinfunction "1_1") (pintype "passive"))
      (node (ref "R30") (pin "2") (pinfunction "2_2") (pintype "passive"))
      (node (ref "R4") (pin "2") (pinfunction "2_2") (pintype "passive"))
      (node (ref "R6") (pin "2") (pinfunction "2_2") (pintype "passive"))
      (node (ref "R8") (pin "2") (pinfunction "2_2") (pintype "passive"))
      (node (ref "U2") (pin "13") (pinfunction "GND_13") (pintype "power_in"))
      (node (ref "U2") (pin "5") (pinfunction "GND_2_5") (pintype "power_in"))
      (node (ref "U4") (pin "2") (pinfunction "GND_2") (pintype "power_in"))
      (node (ref "U5") (pin "21") (pinfunction "GPOGND_21") (pintype "passive"))
      (node (ref "U5") (pin "29") (pinfunction "DGND_29") (pintype "passive"))
      (node (ref "U5") (pin "33") (pinfunction "EPAD_33") (pintype "passive"))
      (node (ref "U5") (pin "4") (pinfunction "AVSS_4") (pintype "passive"))
      (node (ref "U5") (pin "6") (pinfunction "REFN_6") (pintype "passive"))
      (node (ref "U5") (pin "P$1") (pinfunction "EPAD_P$1") (pintype "passive"))
      (node (ref "U5") (pin "P$2") (pinfunction "EPAD_P$2") (pintype "passive"))
      (node (ref "U5") (pin "P$3") (pinfunction "EPAD_P$3") (pintype "passive"))
      (node (ref "U5") (pin "P$4") (pinfunction "EPAD_P$4") (pintype "passive"))
      (node (ref "U5") (pin "P$5") (pinfunction "EPAD_P$5") (pintype "passive"))
      (node (ref "U5") (pin "P$6") (pinfunction "EPAD_P$6") (pintype "passive"))
      (node (ref "U5") (pin "P$7") (pinfunction "EPAD_P$7") (pintype "passive"))
      (node (ref "U5") (pin "P$8") (pinfunction "EPAD_P$8") (pintype "passive"))
      (node (ref "U5") (pin "P$9") (pinfunction "EPAD_P$9") (pintype "passive"))
      (node (ref "U6") (pin "5") (pinfunction "GND_2_5") (pintype "passive"))
      (node (ref "U6") (pin "8") (pinfunction "GND_8") (pintype "passive"))
      (node (ref "U6") (pin "9") (pinfunction "EPAD_9") (pintype "passive"))
      (node (ref "U7") (pin "5") (pinfunction "V-_5") (pintype "power_in"))
      (node (ref "U7") (pin "9") (pinfunction "V-_9") (pintype "power_in"))
      (node (ref "U8") (pin "5") (pinfunction "V-_5") (pintype "power_in"))
      (node (ref "U8") (pin "9") (pinfunction "V-_9") (pintype "power_in"))
      (node (ref "USB1") (pin "P$10") (pinfunction "SHIELD_P$10") (pintype "bidirectional"))
      (node (ref "USB1") (pin "P$11") (pinfunction "SHIELD_P$11") (pintype "bidirectional"))
      (node (ref "USB1") (pin "P$5") (pinfunction "GND_P$5") (pintype "bidirectional"))
      (node (ref "USB1") (pin "P$6") (pinfunction "SHIELD_P$6") (pintype "bidirectional"))
      (node (ref "USB1") (pin "P$7") (pinfunction "SHIELD_P$7") (pintype "bidirectional"))
      (node (ref "USB1") (pin "P$8") (pinfunction "SHIELD_P$8") (pintype "bidirectional"))
      (node (ref "USB1") (pin "P$9") (pinfunction "SHIELD_P$9") (pintype "bidirectional"))
    )
    (net (code "52") (name "Net-(C30-Pad2)") (class "Default")
      (node (ref "C30") (pin "2") (pinfunction "2_2") (pintype "passive"))
      (node (ref "R14") (pin "2") (pinfunction "2_2") (pintype "passive"))
      (node (ref "R16") (pin "1") (pinfunction "1_1") (pintype "passive"))
    )
    (net (code "53") (name "Net-(C31-Pad2)") (class "Default")
      (node (ref "C31") (pin "2") (pinfunction "2_2") (pintype "passive"))
      (node (ref "R14") (pin "1") (pinfunction "1_1") (pintype "passive"))
      (node (ref "R15") (pin "1") (pinfunction "1_1") (pintype "passive"))
    )
    (net (code "54") (name "Net-(J2.1-P$1)") (class "Default")
      (node (ref "J2.1") (pin "1") (pinfunction "P$1_1") (pintype "bidirectional"))
      (node (ref "J2.2") (pin "2") (pinfunction "P$2_2") (pintype "bidirectional"))
      (node (ref "Q1") (pin "13") (pinfunction "MEMS_OUT_13") (pintype "bidirectional"))
    )
    (net (code "55") (name "Net-(LED1-PadC)") (class "Default")
      (node (ref "LED1") (pin "C") (pinfunction "C_C") (pintype "passive"))
      (node (ref "R9") (pin "2") (pinfunction "2_2") (pintype "passive"))
    )
    (net (code "56") (name "Net-(LED2-PadC)") (class "Default")
      (node (ref "LED2") (pin "C") (pinfunction "C_C") (pintype "passive"))
      (node (ref "R12") (pin "2") (pinfunction "2_2") (pintype "passive"))
    )
    (net (code "57") (name "Net-(U2-CBUS1)") (class "Default")
      (node (ref "R12") (pin "1") (pinfunction "1_1") (pintype "passive"))
      (node (ref "U2") (pin "14") (pinfunction "CBUS1_14") (pintype "bidirectional"))
    )
    (net (code "58") (name "Net-(U2-CBUS2)") (class "Default")
      (node (ref "R9") (pin "1") (pinfunction "1_1") (pintype "passive"))
      (node (ref "U2") (pin "7") (pinfunction "CBUS2_7") (pintype "bidirectional"))
    )
    (net (code "59") (name "Net-(U2-USBDM)") (class "Default")
      (node (ref "C2") (pin "2") (pinfunction "2_2") (pintype "passive"))
      (node (ref "U2") (pin "9") (pinfunction "USBDM_9") (pintype "input"))
      (node (ref "USB1") (pin "P$2") (pinfunction "D-_P$2") (pintype "bidirectional"))
    )
    (net (code "60") (name "Net-(U2-USBDP)") (class "Default")
      (node (ref "C4") (pin "2") (pinfunction "2_2") (pintype "passive"))
      (node (ref "U2") (pin "8") (pinfunction "USBDP_8") (pintype "input"))
      (node (ref "USB1") (pin "P$3") (pinfunction "D+_P$3") (pintype "bidirectional"))
    )
    (net (code "61") (name "Net-(U2-~{CTS})") (class "Default")
      (node (ref "U2") (pin "2") (pinfunction "~{RTS}_2") (pintype "output"))
      (node (ref "U2") (pin "6") (pinfunction "~{CTS}_6") (pintype "input"))
    )
    (net (code "62") (name "Net-(U4-FILTER)") (class "Default")
      (node (ref "C12") (pin "2") (pinfunction "2_2") (pintype "passive"))
      (node (ref "U4") (pin "1") (pinfunction "FILTER_1") (pintype "input"))
    )
    (net (code "63") (name "Net-(U5-CAPN)") (class "Default")
      (node (ref "C25") (pin "1") (pinfunction "1_1") (pintype "passive"))
      (node (ref "U5") (pin "19") (pinfunction "CAPN_19") (pintype "passive"))
    )
    (net (code "64") (name "Net-(U5-CAPP)") (class "Default")
      (node (ref "C25") (pin "2") (pinfunction "2_2") (pintype "passive"))
      (node (ref "U5") (pin "20") (pinfunction "CAPP_20") (pintype "passive"))
    )
    (net (code "65") (name "Net-(U5-CAPREG)") (class "Default")
      (node (ref "C34") (pin "2") (pinfunction "2_2") (pintype "passive"))
      (node (ref "U5") (pin "26") (pinfunction "CAPREG_26") (pintype "passive"))
    )
    (net (code "66") (name "Net-(U6-CCAP)") (class "Default")
      (node (ref "C29") (pin "2") (pinfunction "2_2") (pintype "passive"))
      (node (ref "U6") (pin "3") (pinfunction "CCAP_3") (pintype "passive"))
    )
    (net (code "67") (name "Net-(U6-OUT+)") (class "Default")
      (node (ref "C31") (pin "1") (pinfunction "1_1") (pintype "passive"))
      (node (ref "U6") (pin "6") (pinfunction "OUT+_6") (pintype "output"))
    )
    (net (code "68") (name "Net-(U6-OUT-)") (class "Default")
      (node (ref "C30") (pin "1") (pinfunction "1_1") (pintype "passive"))
      (node (ref "U6") (pin "7") (pinfunction "OUT-_7") (pintype "output"))
    )
    (net (code "69") (name "unconnected-(IC1-P1.0{slash}UCB0STE{slash}SMCLK{slash}COMP0.0{slash}A0{slash}VEREF+-Pad3)") (class "Default")
      (node (ref "IC1") (pin "3") (pinfunction "P1.0/UCB0STE/SMCLK/COMP0.0/A0/VEREF+_3") (pintype "bidirectional"))
    )
    (net (code "70") (name "unconnected-(IC1-P1.3{slash}UCB0SOMI{slash}UCB0SCL{slash}OA0+{slash}A3-Pad48)") (class "Default")
      (node (ref "IC1") (pin "48") (pinfunction "P1.3/UCB0SOMI/UCB0SCL/OA0+/A3_48") (pintype "bidirectional"))
    )
    (net (code "71") (name "unconnected-(IC1-P1.4{slash}UCA0STE{slash}TCK{slash}A4-Pad34)") (class "Default")
      (node (ref "IC1") (pin "34") (pinfunction "P1.4/UCA0STE/TCK/A4_34") (pintype "bidirectional"))
    )
    (net (code "72") (name "unconnected-(IC1-P1.5{slash}UCA0CLK{slash}TMS{slash}OA1O{slash}A5-Pad33)") (class "Default")
      (node (ref "IC1") (pin "33") (pinfunction "P1.5/UCA0CLK/TMS/OA1O/A5_33") (pintype "bidirectional"))
    )
    (net (code "73") (name "unconnected-(IC1-P1.6{slash}UCA0RXD{slash}UCA0SOMI{slash}TB0.1{slash}TDI{slash}TCLK{slash}OA1-{slash}A6-Pad32)") (class "Default")
      (node (ref "IC1") (pin "32") (pinfunction "P1.6/UCA0RXD/UCA0SOMI/TB0.1/TDI/TCLK/OA1-/A6_32") (pintype "bidirectional"))
    )
    (net (code "74") (name "unconnected-(IC1-P1.7{slash}UCA0TXD{slash}UCA0SIMO{slash}TB0.2{slash}TDO{slash}OA1+{slash}A7{slash}VREF+-Pad31)") (class "Default")
      (node (ref "IC1") (pin "31") (pinfunction "P1.7/UCA0TXD/UCA0SIMO/TB0.2/TDO/OA1+/A7/VREF+_31") (pintype "bidirectional"))
    )
    (net (code "75") (name "unconnected-(IC1-P2.0{slash}TB1.1{slash}COMP0.O-Pad30)") (class "Default")
      (node (ref "IC1") (pin "30") (pinfunction "P2.0/TB1.1/COMP0.O_30") (pintype "bidirectional"))
    )
    (net (code "76") (name "unconnected-(IC1-P2.1{slash}TB1.2{slash}COMP1.O-Pad29)") (class "Default")
      (node (ref "IC1") (pin "29") (pinfunction "P2.1/TB1.2/COMP1.O_29") (pintype "bidirectional"))
    )
    (net (code "77") (name "unconnected-(IC1-P2.2{slash}TB1CLK-Pad28)") (class "Default")
      (node (ref "IC1") (pin "28") (pinfunction "P2.2/TB1CLK_28") (pintype "bidirectional"))
    )
    (net (code "78") (name "unconnected-(IC1-P2.3{slash}TB1TRG-Pad27)") (class "Default")
      (node (ref "IC1") (pin "27") (pinfunction "P2.3/TB1TRG_27") (pintype "bidirectional"))
    )
    (net (code "79") (name "unconnected-(IC1-P2.4{slash}COMP1.1-Pad11)") (class "Default")
      (node (ref "IC1") (pin "11") (pinfunction "P2.4/COMP1.1_11") (pintype "bidirectional"))
    )
    (net (code "80") (name "unconnected-(IC1-P2.5{slash}COMP1.0-Pad10)") (class "Default")
      (node (ref "IC1") (pin "10") (pinfunction "P2.5/COMP1.0_10") (pintype "bidirectional"))
    )
    (net (code "81") (name "unconnected-(IC1-P2.6{slash}MCLK{slash}XOUT-Pad9)") (class "Default")
      (node (ref "IC1") (pin "9") (pinfunction "P2.6/MCLK/XOUT_9") (pintype "bidirectional"))
    )
    (net (code "82") (name "unconnected-(IC1-P2.7{slash}TB0CLK{slash}XIN-Pad8)") (class "Default")
      (node (ref "IC1") (pin "8") (pinfunction "P2.7/TB0CLK/XIN_8") (pintype "bidirectional"))
    )
    (net (code "83") (name "unconnected-(IC1-P3.0{slash}MCLK-Pad47)") (class "Default")
      (node (ref "IC1") (pin "47") (pinfunction "P3.0/MCLK_47") (pintype "bidirectional"))
    )
    (net (code "84") (name "unconnected-(IC1-P3.3{slash}OA2+-Pad44)") (class "Default")
      (node (ref "IC1") (pin "44") (pinfunction "P3.3/OA2+_44") (pintype "bidirectional"))
    )
    (net (code "85") (name "unconnected-(IC1-P3.4{slash}SMCLK-Pad38)") (class "Default")
      (node (ref "IC1") (pin "38") (pinfunction "P3.4/SMCLK_38") (pintype "bidirectional"))
    )
    (net (code "86") (name "unconnected-(IC1-P3.5{slash}OA3O-Pad37)") (class "Default")
      (node (ref "IC1") (pin "37") (pinfunction "P3.5/OA3O_37") (pintype "bidirectional"))
    )
    (net (code "87") (name "unconnected-(IC1-P4.0{slash}UCA1STE{slash}ISOTXD{slash}ISORXD-Pad26)") (class "Default")
      (node (ref "IC1") (pin "26") (pinfunction "P4.0/UCA1STE/ISOTXD/ISORXD_26") (pintype "bidirectional"))
    )
    (net (code "88") (name "unconnected-(IC1-P4.1{slash}UCA1CLK-Pad25)") (class "Default")
      (node (ref "IC1") (pin "25") (pinfunction "P4.1/UCA1CLK_25") (pintype "bidirectional"))
    )
    (net (code "89") (name "unconnected-(IC1-P5.0{slash}TB2.1{slash}MFM.RX{slash}A8-Pad43)") (class "Default")
      (node (ref "IC1") (pin "43") (pinfunction "P5.0/TB2.1/MFM.RX/A8_43") (pintype "bidirectional"))
    )
    (net (code "90") (name "unconnected-(IC1-P5.1{slash}TB2.2{slash}MFM.TX{slash}A9-Pad42)") (class "Default")
      (node (ref "IC1") (pin "42") (pinfunction "P5.1/TB2.2/MFM.TX/A9_42") (pintype "bidirectional"))
    )
    (net (code "91") (name "unconnected-(IC1-P5.2{slash}TB2CLK{slash}A10-Pad41)") (class "Default")
      (node (ref "IC1") (pin "41") (pinfunction "P5.2/TB2CLK/A10_41") (pintype "bidirectional"))
    )
    (net (code "92") (name "unconnected-(IC1-P5.3{slash}TB2TRG{slash}A11-Pad40)") (class "Default")
      (node (ref "IC1") (pin "40") (pinfunction "P5.3/TB2TRG/A11_40") (pintype "bidirectional"))
    )
    (net (code "93") (name "unconnected-(IC1-P5.4-Pad39)") (class "Default")
      (node (ref "IC1") (pin "39") (pinfunction "P5.4_39") (pintype "bidirectional"))
    )
    (net (code "94") (name "unconnected-(IC1-P6.0{slash}TB3.1-Pad22)") (class "Default")
      (node (ref "IC1") (pin "22") (pinfunction "P6.0/TB3.1_22") (pintype "bidirectional"))
    )
    (net (code "95") (name "unconnected-(IC1-P6.1{slash}TB3.2-Pad21)") (class "Default")
      (node (ref "IC1") (pin "21") (pinfunction "P6.1/TB3.2_21") (pintype "bidirectional"))
    )
    (net (code "96") (name "unconnected-(IC1-P6.2{slash}TB3.3-Pad20)") (class "Default")
      (node (ref "IC1") (pin "20") (pinfunction "P6.2/TB3.3_20") (pintype "bidirectional"))
    )
    (net (code "97") (name "unconnected-(IC1-P6.3{slash}TB3.4-Pad19)") (class "Default")
      (node (ref "IC1") (pin "19") (pinfunction "P6.3/TB3.4_19") (pintype "bidirectional"))
    )
    (net (code "98") (name "unconnected-(IC1-P6.4{slash}TB3.5-Pad18)") (class "Default")
      (node (ref "IC1") (pin "18") (pinfunction "P6.4/TB3.5_18") (pintype "bidirectional"))
    )
    (net (code "99") (name "unconnected-(IC1-P6.6{slash}TB3CLK-Pad16)") (class "Default")
      (node (ref "IC1") (pin "16") (pinfunction "P6.6/TB3CLK_16") (pintype "bidirectional"))
    )
    (net (code "100") (name "unconnected-(U2-CBUS0-Pad15)") (class "Default")
      (node (ref "U2") (pin "15") (pinfunction "CBUS0_15") (pintype "bidirectional"))
    )
    (net (code "101") (name "unconnected-(U2-CBUS3-Pad16)") (class "Default")
      (node (ref "U2") (pin "16") (pinfunction "CBUS3_16") (pintype "bidirectional"))
    )
    (net (code "102") (name "unconnected-(U5-AIN4N-Pad15)") (class "Default")
      (node (ref "U5") (pin "15") (pinfunction "AIN4N_15") (pintype "input"))
    )
    (net (code "103") (name "unconnected-(U5-AIN4P-Pad16)") (class "Default")
      (node (ref "U5") (pin "16") (pinfunction "AIN4P_16") (pintype "input"))
    )
    (net (code "104") (name "unconnected-(U5-AIN5N-Pad17)") (class "Default")
      (node (ref "U5") (pin "17") (pinfunction "AIN5N_17") (pintype "input"))
    )
    (net (code "105") (name "unconnected-(U5-AIN5P-Pad18)") (class "Default")
      (node (ref "U5") (pin "18") (pinfunction "AIN5P_18") (pintype "input"))
    )
    (net (code "106") (name "unconnected-(U5-GPIO0{slash}CLK-Pad23)") (class "Default")
      (node (ref "U5") (pin "23") (pinfunction "GPIO0/CLK_23") (pintype "bidirectional"))
    )
    (net (code "107") (name "unconnected-(U5-GPIO1{slash}SYNC-Pad25)") (class "Default")
      (node (ref "U5") (pin "25") (pinfunction "GPIO1/SYNC_25") (pintype "bidirectional"))
    )
    (net (code "108") (name "unconnected-(U5-GPO0-Pad24)") (class "Default")
      (node (ref "U5") (pin "24") (pinfunction "GPO0_24") (pintype "bidirectional"))
    )
    (net (code "109") (name "unconnected-(U5-GPO1-Pad22)") (class "Default")
      (node (ref "U5") (pin "22") (pinfunction "GPO1_22") (pintype "bidirectional"))
    )
    (net (code "110") (name "unconnected-(U6-OFFSET-Pad4)") (class "Default")
      (node (ref "U6") (pin "4") (pinfunction "OFFSET_4") (pintype "passive"))
    )
    (net (code "111") (name "unconnected-(USB1-ID-PadP$4)") (class "Default")
      (node (ref "USB1") (pin "P$4") (pinfunction "ID_P$4") (pintype "bidirectional"))
    )
  )
)
